# Wireless.net
KiCad netlist of a schematic drawn in Altium Designer
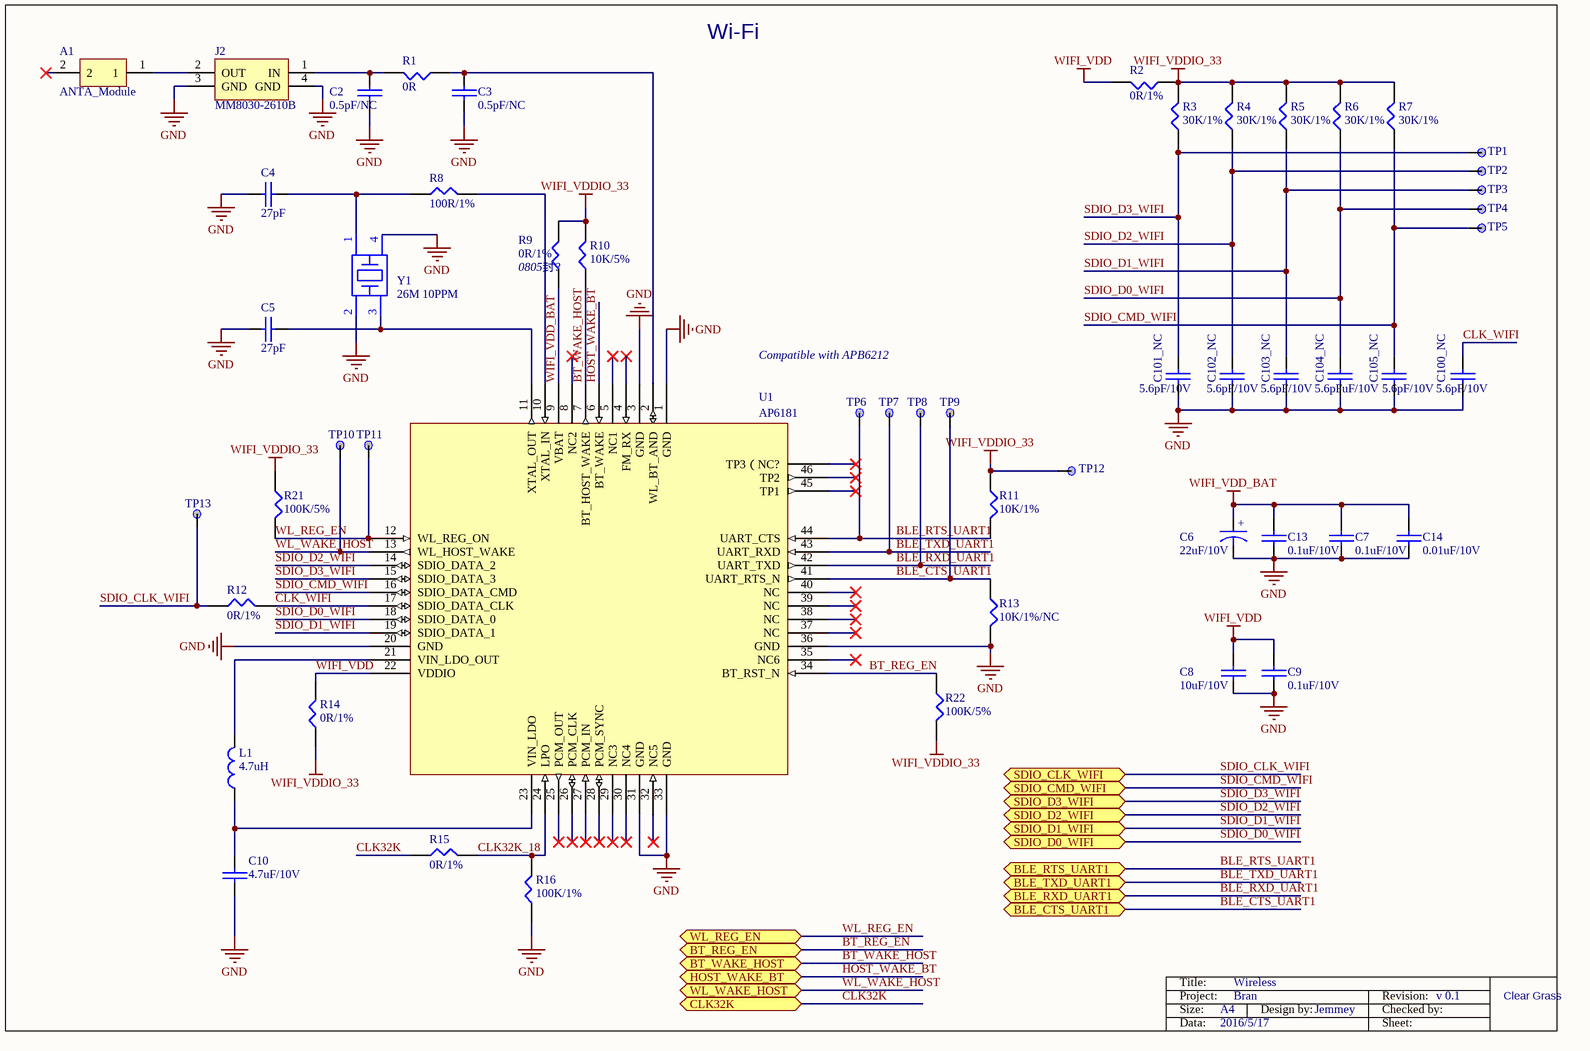
[diagram p0: Wireless.SchDoc]

(export (version "E")
  (design (tool "Eeschema 10.0.6"))
  (components
    (comp (ref "A1")
      (value "ANTA_Module")
      (footprint "IPEX")
      (libsource (lib "Bran MB") (part "ANTA_Module"))
    )
    (comp (ref "C2")
      (value "0.5pF/NC")
      (footprint "0402C")
      (description "厂家：Murata，型号：GRM1555C1H1R0BA01D")
      (libsource (lib "*") (part "CAP"))
    )
    (comp (ref "C3")
      (value "0.5pF/NC")
      (footprint "0402C")
      (description "None")
      (libsource (lib "*") (part "CAP"))
    )
    (comp (ref "C4")
      (value "27pF")
      (footprint "0402C")
      (description "厂家：Murata，型号：GRM155R71A104KA01D")
      (libsource (lib "*") (part "CAP"))
    )
    (comp (ref "C5")
      (value "27pF")
      (footprint "0402C")
      (description "厂家：Murata，型号：GRM155R71A104KA01D")
      (libsource (lib "*") (part "CAP"))
    )
    (comp (ref "C6") (value "22uF/10V") (footprint "6032") (libsource (lib "MoJi LIB") (part "Capacitor")))
    (comp (ref "C7")
      (value "0.1uF/10V")
      (footprint "0402C")
      (description "厂家：Murata，型号：GRM155R71A104KA01D")
      (libsource (lib "Amber") (part "CAP"))
    )
    (comp (ref "C8")
      (value "10uF/10V")
      (footprint "0402C")
      (description "厂家：Murata，型号：GRM155R71A104KA01D")
      (libsource (lib "Amber") (part "CAP"))
    )
    (comp (ref "C9")
      (value "0.1uF/10V")
      (footprint "0402C")
      (description "厂家：Murata，型号：GRM155R71A104KA01D")
      (libsource (lib "Amber") (part "CAP"))
    )
    (comp (ref "C10")
      (value "4.7uF/10V")
      (footprint "0402C")
      (description "厂家：Murata，型号：GRM155R71A104KA01D")
      (libsource (lib "*") (part "CAP"))
    )
    (comp (ref "C13")
      (value "0.1uF/10V")
      (footprint "0402C")
      (description "厂家：Murata，型号：GRM155R71A104KA01D")
      (libsource (lib "Amber") (part "CAP"))
    )
    (comp (ref "C14")
      (value "0.01uF/10V")
      (footprint "0402C")
      (description "厂家：Murata，型号：GRM155R71A104KA01D")
      (libsource (lib "Amber") (part "CAP"))
    )
    (comp (ref "C100_NC")
      (value "5.6pF/10V")
      (footprint "0402C")
      (description "厂家：Murata，型号：GRM155R71A104KA01D")
      (libsource (lib "Amber") (part "CAP"))
    )
    (comp (ref "C101_NC")
      (value "5.6pF/10V")
      (footprint "0402C")
      (description "厂家：Murata，型号：GRM155R71A104KA01D")
      (libsource (lib "Amber") (part "CAP"))
    )
    (comp (ref "C102_NC")
      (value "5.6pF/10V")
      (footprint "0402C")
      (description "厂家：Murata，型号：GRM155R71A104KA01D")
      (libsource (lib "Amber") (part "CAP"))
    )
    (comp (ref "C103_NC")
      (value "5.6pF/10V")
      (footprint "0402C")
      (description "厂家：Murata，型号：GRM155R71A104KA01D")
      (libsource (lib "Amber") (part "CAP"))
    )
    (comp (ref "C104_NC")
      (value "5.6pFuF/10V")
      (footprint "0402C")
      (description "厂家：Murata，型号：GRM155R71A104KA01D")
      (libsource (lib "Amber") (part "CAP"))
    )
    (comp (ref "C105_NC")
      (value "5.6pF/10V")
      (footprint "0402C")
      (description "厂家：Murata，型号：GRM155R71A104KA01D")
      (libsource (lib "Amber") (part "CAP"))
    )
    (comp (ref "J2")
      (value "MM8030-2610B")
      (footprint "IPEX")
      (description "厂家：Murata，型号：MM8030-2610B")
      (libsource (lib "Bran MB") (part "SMA"))
    )
    (comp (ref "L1") (value "4.7uH") (footprint "Inductance") (libsource (lib "*") (part "CHOKE")))
    (comp (ref "R1")
      (value "0R")
      (footprint "0402R")
      (description "厂家：Yageo，型号：RC0402FR-070RL")
      (libsource (lib "*") (part "RES1"))
    )
    (comp (ref "R2")
      (value "0R/1%")
      (footprint "0402R")
      (description "厂家：Yageo，型号：RC0402FR-0710KL")
      (libsource (lib "*") (part "RES1"))
    )
    (comp (ref "R3")
      (value "30K/1%")
      (footprint "0402R")
      (description "厂家：Yageo，型号：RC0402FR-0710KL")
      (libsource (lib "*") (part "RES1"))
    )
    (comp (ref "R4")
      (value "30K/1%")
      (footprint "0402R")
      (description "厂家：Yageo，型号：RC0402FR-0710KL")
      (libsource (lib "*") (part "RES1"))
    )
    (comp (ref "R5")
      (value "30K/1%")
      (footprint "0402R")
      (description "厂家：Yageo，型号：RC0402FR-0710KL")
      (libsource (lib "*") (part "RES1"))
    )
    (comp (ref "R6")
      (value "30K/1%")
      (footprint "0402R")
      (description "厂家：Yageo，型号：RC0402FR-0710KL")
      (libsource (lib "*") (part "RES1"))
    )
    (comp (ref "R7")
      (value "30K/1%")
      (footprint "0402R")
      (description "厂家：Yageo，型号：RC0402FR-0710KL")
      (libsource (lib "*") (part "RES1"))
    )
    (comp (ref "R8")
      (value "100R/1%")
      (footprint "0402R")
      (description "厂家：Yageo，型号：RC0402FR-0710KL")
      (libsource (lib "*") (part "RES1"))
    )
    (comp (ref "R9")
      (value "0R/1%")
      (footprint "0402R")
      (description "厂家：Yageo，型号：RC0402FR-0710KL")
      (libsource (lib "*") (part "RES1"))
    )
    (comp (ref "R10")
      (value "10K/5%")
      (footprint "0402R")
      (description "厂家：Yageo，型号：RC0402FR-0710KL")
      (libsource (lib "*") (part "RES1"))
    )
    (comp (ref "R11")
      (value "10K/1%")
      (footprint "0402R")
      (description "厂家：Yageo，型号：RC0402FR-0710KL")
      (libsource (lib "*") (part "RES1"))
    )
    (comp (ref "R12")
      (value "0R/1%")
      (footprint "0402R")
      (description "厂家：Yageo，型号：RC0402FR-0710KL")
      (libsource (lib "*") (part "RES1"))
    )
    (comp (ref "R13")
      (value "10K/1%/NC")
      (footprint "0402R")
      (description "厂家：Yageo，型号：RC0402FR-0710KL")
      (libsource (lib "*") (part "RES1"))
    )
    (comp (ref "R14")
      (value "0R/1%")
      (footprint "0402R")
      (description "厂家：Yageo，型号：RC0402FR-0710KL")
      (libsource (lib "*") (part "RES1"))
    )
    (comp (ref "R15")
      (value "0R/1%")
      (footprint "0402R")
      (description "厂家：Yageo，型号：RC0402FR-0710KL")
      (libsource (lib "*") (part "RES1"))
    )
    (comp (ref "R16")
      (value "100K/1%")
      (footprint "0402R")
      (description "厂家：Yageo，型号：RC0402FR-0710KL")
      (libsource (lib "*") (part "RES1"))
    )
    (comp (ref "R21")
      (value "100K/5%")
      (footprint "0402R")
      (description "厂家：Yageo，型号：RC0402FR-0710KL")
      (libsource (lib "*") (part "RES1"))
    )
    (comp (ref "R22")
      (value "100K/5%")
      (footprint "0402R")
      (description "厂家：Yageo，型号：RC0402FR-0710KL")
      (libsource (lib "*") (part "RES1"))
    )
    (comp (ref "TP1") (value "TP") (footprint "TP_C40") (libsource (lib "Almos") (part "TP")))
    (comp (ref "TP2") (value "TP") (footprint "TP_C40") (libsource (lib "Almos") (part "TP")))
    (comp (ref "TP3") (value "TP") (footprint "TP_C40") (libsource (lib "Almos") (part "TP")))
    (comp (ref "TP4") (value "TP") (footprint "TP_C40") (libsource (lib "Almos") (part "TP")))
    (comp (ref "TP5") (value "TP") (footprint "TP_C40") (libsource (lib "Almos") (part "TP")))
    (comp (ref "TP6") (value "TP") (footprint "TP_C40") (libsource (lib "Almos") (part "TP")))
    (comp (ref "TP7") (value "TP") (footprint "TP_C40") (libsource (lib "Almos") (part "TP")))
    (comp (ref "TP8") (value "TP") (footprint "TP_C40") (libsource (lib "Almos") (part "TP")))
    (comp (ref "TP9") (value "TP") (footprint "TP_C40") (libsource (lib "Almos") (part "TP")))
    (comp (ref "TP10") (value "TP") (footprint "TP_C40") (libsource (lib "Almos") (part "TP")))
    (comp (ref "TP11") (value "TP") (footprint "TP_C40") (libsource (lib "Almos") (part "TP")))
    (comp (ref "TP12") (value "TP") (footprint "TP_C40") (libsource (lib "Almos") (part "TP")))
    (comp (ref "TP13") (value "TP") (footprint "TP_C40") (libsource (lib "Almos") (part "TP")))
    (comp (ref "U1")
      (value "AP6181")
      (description "厂家：正基，型号：AP6181")
      (libsource (lib "Bran MB") (part "AP6181"))
    )
    (comp (ref "Y1")
      (value "26M 10PPM")
      (footprint "XTALSMD2-2520")
      (description "厂家：EPSON，型号：Q24FA20H0004400")
      (libsource (lib "Amber_1") (part "CRYSTAL2"))
    )
  )
  (nets
    (net (code "1") (name "/BLE_CTS_UART1") (class "Default")
      (node (ref "R13") (pin "1") (pinfunction "1_1") (pintype "passive"))
      (node (ref "TP9") (pin "1") (pinfunction "1_1") (pintype "passive"))
      (node (ref "U1") (pin "41") (pinfunction "UART_RTS_N_41") (pintype "output"))
    )
    (net (code "2") (name "/BLE_RTS_UART1") (class "Default")
      (node (ref "R11") (pin "2") (pinfunction "2_2") (pintype "passive"))
      (node (ref "TP6") (pin "1") (pinfunction "1_1") (pintype "passive"))
      (node (ref "U1") (pin "44") (pinfunction "UART_CTS_44") (pintype "input"))
    )
    (net (code "3") (name "/BLE_RXD_UART1") (class "Default")
      (node (ref "TP8") (pin "1") (pinfunction "1_1") (pintype "passive"))
      (node (ref "U1") (pin "42") (pinfunction "UART_TXD_42") (pintype "output"))
    )
    (net (code "4") (name "/BLE_TXD_UART1") (class "Default")
      (node (ref "TP7") (pin "1") (pinfunction "1_1") (pintype "passive"))
      (node (ref "U1") (pin "43") (pinfunction "UART_RXD_43") (pintype "input"))
    )
    (net (code "5") (name "/BT_REG_EN") (class "Default")
      (node (ref "R22") (pin "1") (pinfunction "1_1") (pintype "passive"))
      (node (ref "U1") (pin "34") (pinfunction "BT_RST_N_34") (pintype "input"))
    )
    (net (code "6") (name "/BT_WAKE_HOST") (class "Default")
      (node (ref "R10") (pin "1") (pinfunction "1_1") (pintype "passive"))
      (node (ref "U1") (pin "7") (pinfunction "BT_HOST_WAKE_7") (pintype "output"))
    )
    (net (code "7") (name "/CLK32K") (class "Default")
      (node (ref "R15") (pin "1") (pinfunction "1_1") (pintype "passive"))
    )
    (net (code "8") (name "/CLK32K_18") (class "Default")
      (node (ref "R15") (pin "2") (pinfunction "2_2") (pintype "passive"))
      (node (ref "R16") (pin "2") (pinfunction "2_2") (pintype "passive"))
      (node (ref "U1") (pin "24") (pinfunction "LPO_24") (pintype "input"))
    )
    (net (code "9") (name "/CLK_WIFI") (class "Default")
      (node (ref "C100_NC") (pin "2") (pinfunction "2_2") (pintype "passive"))
      (node (ref "R12") (pin "2") (pinfunction "2_2") (pintype "passive"))
      (node (ref "U1") (pin "17") (pinfunction "SDIO_DATA_CLK_17") (pintype "bidirectional"))
    )
    (net (code "10") (name "/HOST_WAKE_BT") (class "Default")
      (node (ref "U1") (pin "6") (pinfunction "BT_WAKE_6") (pintype "input"))
    )
    (net (code "11") (name "/SDIO_CLK_WIFI") (class "Default")
      (node (ref "R12") (pin "1") (pinfunction "1_1") (pintype "passive"))
      (node (ref "TP13") (pin "1") (pinfunction "1_1") (pintype "passive"))
    )
    (net (code "12") (name "/SDIO_CMD_WIFI") (class "Default")
      (node (ref "C105_NC") (pin "2") (pinfunction "2_2") (pintype "passive"))
      (node (ref "R7") (pin "1") (pinfunction "1_1") (pintype "passive"))
      (node (ref "TP5") (pin "1") (pinfunction "1_1") (pintype "passive"))
      (node (ref "U1") (pin "16") (pinfunction "SDIO_DATA_CMD_16") (pintype "bidirectional"))
    )
    (net (code "13") (name "/SDIO_D0_WIFI") (class "Default")
      (node (ref "C104_NC") (pin "2") (pinfunction "2_2") (pintype "passive"))
      (node (ref "R6") (pin "1") (pinfunction "1_1") (pintype "passive"))
      (node (ref "TP4") (pin "1") (pinfunction "1_1") (pintype "passive"))
      (node (ref "U1") (pin "18") (pinfunction "SDIO_DATA_0_18") (pintype "bidirectional"))
    )
    (net (code "14") (name "/SDIO_D1_WIFI") (class "Default")
      (node (ref "C103_NC") (pin "2") (pinfunction "2_2") (pintype "passive"))
      (node (ref "R5") (pin "1") (pinfunction "1_1") (pintype "passive"))
      (node (ref "TP3") (pin "1") (pinfunction "1_1") (pintype "passive"))
      (node (ref "U1") (pin "19") (pinfunction "SDIO_DATA_1_19") (pintype "bidirectional"))
    )
    (net (code "15") (name "/SDIO_D2_WIFI") (class "Default")
      (node (ref "C102_NC") (pin "2") (pinfunction "2_2") (pintype "passive"))
      (node (ref "R4") (pin "1") (pinfunction "1_1") (pintype "passive"))
      (node (ref "TP2") (pin "1") (pinfunction "1_1") (pintype "passive"))
      (node (ref "U1") (pin "14") (pinfunction "SDIO_DATA_2_14") (pintype "bidirectional"))
    )
    (net (code "16") (name "/SDIO_D3_WIFI") (class "Default")
      (node (ref "C101_NC") (pin "2") (pinfunction "2_2") (pintype "passive"))
      (node (ref "R3") (pin "1") (pinfunction "1_1") (pintype "passive"))
      (node (ref "TP1") (pin "1") (pinfunction "1_1") (pintype "passive"))
      (node (ref "U1") (pin "15") (pinfunction "SDIO_DATA_3_15") (pintype "bidirectional"))
    )
    (net (code "17") (name "/WL_REG_EN") (class "Default")
      (node (ref "R21") (pin "2") (pinfunction "2_2") (pintype "passive"))
      (node (ref "TP11") (pin "1") (pinfunction "1_1") (pintype "passive"))
      (node (ref "U1") (pin "12") (pinfunction "WL_REG_ON_12") (pintype "input"))
    )
    (net (code "18") (name "/WL_WAKE_HOST") (class "Default")
      (node (ref "TP10") (pin "1") (pinfunction "1_1") (pintype "passive"))
      (node (ref "U1") (pin "13") (pinfunction "WL_HOST_WAKE_13") (pintype "output"))
    )
    (net (code "19") (name "GND") (class "Default")
      (node (ref "C10") (pin "2") (pinfunction "2_2") (pintype "passive"))
      (node (ref "C100_NC") (pin "1") (pinfunction "1_1") (pintype "passive"))
      (node (ref "C101_NC") (pin "1") (pinfunction "1_1") (pintype "passive"))
      (node (ref "C102_NC") (pin "1") (pinfunction "1_1") (pintype "passive"))
      (node (ref "C103_NC") (pin "1") (pinfunction "1_1") (pintype "passive"))
      (node (ref "C104_NC") (pin "1") (pinfunction "1_1") (pintype "passive"))
      (node (ref "C105_NC") (pin "1") (pinfunction "1_1") (pintype "passive"))
      (node (ref "C13") (pin "1") (pinfunction "1_1") (pintype "passive"))
      (node (ref "C14") (pin "1") (pinfunction "1_1") (pintype "passive"))
      (node (ref "C2") (pin "2") (pinfunction "2_2") (pintype "passive"))
      (node (ref "C3") (pin "2") (pinfunction "2_2") (pintype "passive"))
      (node (ref "C4") (pin "1") (pinfunction "1_1") (pintype "passive"))
      (node (ref "C5") (pin "1") (pinfunction "1_1") (pintype "passive"))
      (node (ref "C6") (pin "2") (pinfunction "2_2") (pintype "passive"))
      (node (ref "C7") (pin "1") (pinfunction "1_1") (pintype "passive"))
      (node (ref "C8") (pin "1") (pinfunction "1_1") (pintype "passive"))
      (node (ref "C9") (pin "1") (pinfunction "1_1") (pintype "passive"))
      (node (ref "J2") (pin "3") (pinfunction "GND_3") (pintype "passive"))
      (node (ref "J2") (pin "4") (pinfunction "GND_4") (pintype "passive"))
      (node (ref "R13") (pin "2") (pinfunction "2_2") (pintype "passive"))
      (node (ref "R16") (pin "1") (pinfunction "1_1") (pintype "passive"))
      (node (ref "U1") (pin "1") (pinfunction "GND_1") (pintype "power_in"))
      (node (ref "U1") (pin "20") (pinfunction "GND_20") (pintype "power_in"))
      (node (ref "U1") (pin "3") (pinfunction "GND_3") (pintype "power_in"))
      (node (ref "U1") (pin "31") (pinfunction "GND_31") (pintype "power_in"))
      (node (ref "U1") (pin "33") (pinfunction "GND_33") (pintype "power_in"))
      (node (ref "U1") (pin "36") (pinfunction "GND_36") (pintype "passive"))
      (node (ref "Y1") (pin "2") (pinfunction "2_2") (pintype "passive"))
      (node (ref "Y1") (pin "4") (pinfunction "4_4") (pintype "passive"))
    )
    (net (code "20") (name "Net-(C4-Pad2)") (class "Default")
      (node (ref "C4") (pin "2") (pinfunction "2_2") (pintype "passive"))
      (node (ref "R8") (pin "1") (pinfunction "1_1") (pintype "passive"))
      (node (ref "Y1") (pin "1") (pinfunction "1_1") (pintype "passive"))
    )
    (net (code "21") (name "Net-(J2-IN)") (class "Default")
      (node (ref "C2") (pin "1") (pinfunction "1_1") (pintype "passive"))
      (node (ref "J2") (pin "1") (pinfunction "IN_1") (pintype "passive"))
      (node (ref "R1") (pin "2") (pinfunction "2_2") (pintype "passive"))
    )
    (net (code "22") (name "Net-(J2-OUT)") (class "Default")
      (node (ref "A1") (pin "1") (pinfunction "1_1") (pintype "passive"))
      (node (ref "J2") (pin "2") (pinfunction "OUT_2") (pintype "passive"))
    )
    (net (code "23") (name "Net-(U1-VIN_LDO)") (class "Default")
      (node (ref "C10") (pin "1") (pinfunction "1_1") (pintype "passive"))
      (node (ref "L1") (pin "1") (pinfunction "1_1") (pintype "passive"))
      (node (ref "U1") (pin "23") (pinfunction "VIN_LDO_23") (pintype "power_in"))
    )
    (net (code "24") (name "Net-(U1-VIN_LDO_OUT)") (class "Default")
      (node (ref "L1") (pin "2") (pinfunction "2_2") (pintype "passive"))
      (node (ref "U1") (pin "21") (pinfunction "VIN_LDO_OUT_21") (pintype "power_in"))
    )
    (net (code "25") (name "Net-(U1-WL_BT_AND)") (class "Default")
      (node (ref "C3") (pin "1") (pinfunction "1_1") (pintype "passive"))
      (node (ref "R1") (pin "1") (pinfunction "1_1") (pintype "passive"))
      (node (ref "U1") (pin "2") (pinfunction "WL_BT_AND_2") (pintype "bidirectional"))
    )
    (net (code "26") (name "Net-(U1-XTAL_IN)") (class "Default")
      (node (ref "R8") (pin "2") (pinfunction "2_2") (pintype "passive"))
      (node (ref "U1") (pin "10") (pinfunction "XTAL_IN_10") (pintype "input"))
    )
    (net (code "27") (name "Net-(U1-XTAL_OUT)") (class "Default")
      (node (ref "C5") (pin "2") (pinfunction "2_2") (pintype "passive"))
      (node (ref "U1") (pin "11") (pinfunction "XTAL_OUT_11") (pintype "output"))
      (node (ref "Y1") (pin "3") (pinfunction "3_3") (pintype "passive"))
    )
    (net (code "28") (name "WIFI_VDD") (class "Default")
      (node (ref "C8") (pin "2") (pinfunction "2_2") (pintype "passive"))
      (node (ref "C9") (pin "2") (pinfunction "2_2") (pintype "passive"))
      (node (ref "R14") (pin "2") (pinfunction "2_2") (pintype "passive"))
      (node (ref "R2") (pin "2") (pinfunction "2_2") (pintype "passive"))
      (node (ref "U1") (pin "22") (pinfunction "VDDIO_22") (pintype "power_in"))
    )
    (net (code "29") (name "WIFI_VDDIO_33") (class "Default")
      (node (ref "R10") (pin "2") (pinfunction "2_2") (pintype "passive"))
      (node (ref "R11") (pin "1") (pinfunction "1_1") (pintype "passive"))
      (node (ref "R14") (pin "1") (pinfunction "1_1") (pintype "passive"))
      (node (ref "R2") (pin "1") (pinfunction "1_1") (pintype "passive"))
      (node (ref "R21") (pin "1") (pinfunction "1_1") (pintype "passive"))
      (node (ref "R22") (pin "2") (pinfunction "2_2") (pintype "passive"))
      (node (ref "R3") (pin "2") (pinfunction "2_2") (pintype "passive"))
      (node (ref "R4") (pin "2") (pinfunction "2_2") (pintype "passive"))
      (node (ref "R5") (pin "2") (pinfunction "2_2") (pintype "passive"))
      (node (ref "R6") (pin "2") (pinfunction "2_2") (pintype "passive"))
      (node (ref "R7") (pin "2") (pinfunction "2_2") (pintype "passive"))
      (node (ref "R9") (pin "2") (pinfunction "2_2") (pintype "passive"))
      (node (ref "TP12") (pin "1") (pinfunction "1_1") (pintype "passive"))
    )
    (net (code "30") (name "WIFI_VDD_BAT") (class "Default")
      (node (ref "C13") (pin "2") (pinfunction "2_2") (pintype "passive"))
      (node (ref "C14") (pin "2") (pinfunction "2_2") (pintype "passive"))
      (node (ref "C6") (pin "1") (pinfunction "1_1") (pintype "passive"))
      (node (ref "C7") (pin "2") (pinfunction "2_2") (pintype "passive"))
      (node (ref "R9") (pin "1") (pinfunction "1_1") (pintype "passive"))
      (node (ref "U1") (pin "9") (pinfunction "VBAT_9") (pintype "power_in"))
    )
    (net (code "31") (name "unconnected-(A1-Pad2)") (class "Default")
      (node (ref "A1") (pin "2") (pinfunction "2_2") (pintype "passive+no_connect"))
    )
    (net (code "32") (name "unconnected-(U1-FM_RX-Pad4)") (class "Default")
      (node (ref "U1") (pin "4") (pinfunction "FM_RX_4") (pintype "input+no_connect"))
    )
    (net (code "33") (name "unconnected-(U1-NC-Pad37)") (class "Default")
      (node (ref "U1") (pin "37") (pinfunction "NC_37") (pintype "passive+no_connect"))
    )
    (net (code "34") (name "unconnected-(U1-NC-Pad38)") (class "Default")
      (node (ref "U1") (pin "38") (pinfunction "NC_38") (pintype "passive+no_connect"))
    )
    (net (code "35") (name "unconnected-(U1-NC-Pad39)") (class "Default")
      (node (ref "U1") (pin "39") (pinfunction "NC_39") (pintype "passive+no_connect"))
    )
    (net (code "36") (name "unconnected-(U1-NC-Pad40)") (class "Default")
      (node (ref "U1") (pin "40") (pinfunction "NC_40") (pintype "passive+no_connect"))
    )
    (net (code "37") (name "unconnected-(U1-NC1-Pad5)") (class "Default")
      (node (ref "U1") (pin "5") (pinfunction "NC1_5") (pintype "passive+no_connect"))
    )
    (net (code "38") (name "unconnected-(U1-NC2-Pad8)") (class "Default")
      (node (ref "U1") (pin "8") (pinfunction "NC2_8") (pintype "passive+no_connect"))
    )
    (net (code "39") (name "unconnected-(U1-NC3-Pad29)") (class "Default")
      (node (ref "U1") (pin "29") (pinfunction "NC3_29") (pintype "passive+no_connect"))
    )
    (net (code "40") (name "unconnected-(U1-NC4-Pad30)") (class "Default")
      (node (ref "U1") (pin "30") (pinfunction "NC4_30") (pintype "passive+no_connect"))
    )
    (net (code "41") (name "unconnected-(U1-NC5-Pad32)") (class "Default")
      (node (ref "U1") (pin "32") (pinfunction "NC5_32") (pintype "input+no_connect"))
    )
    (net (code "42") (name "unconnected-(U1-NC6-Pad35)") (class "Default")
      (node (ref "U1") (pin "35") (pinfunction "NC6_35") (pintype "passive+no_connect"))
    )
    (net (code "43") (name "unconnected-(U1-PCM_CLK-Pad26)") (class "Default")
      (node (ref "U1") (pin "26") (pinfunction "PCM_CLK_26") (pintype "bidirectional+no_connect"))
    )
    (net (code "44") (name "unconnected-(U1-PCM_IN-Pad27)") (class "Default")
      (node (ref "U1") (pin "27") (pinfunction "PCM_IN_27") (pintype "input+no_connect"))
    )
    (net (code "45") (name "unconnected-(U1-PCM_OUT-Pad25)") (class "Default")
      (node (ref "U1") (pin "25") (pinfunction "PCM_OUT_25") (pintype "output+no_connect"))
    )
    (net (code "46") (name "unconnected-(U1-PCM_SYNC-Pad28)") (class "Default")
      (node (ref "U1") (pin "28") (pinfunction "PCM_SYNC_28") (pintype "bidirectional+no_connect"))
    )
    (net (code "47") (name "unconnected-(U1-TP1-Pad45)") (class "Default")
      (node (ref "U1") (pin "45") (pinfunction "TP1_45") (pintype "output+no_connect"))
    )
    (net (code "48") (name "unconnected-(U1-TP2-Pad46)") (class "Default")
      (node (ref "U1") (pin "46") (pinfunction "TP2_46") (pintype "output+no_connect"))
    )
    (net (code "49") (name "unconnected-(U1-TP3（NC?-Pad)") (class "Default")
      (node (ref "U1") (pin "") (pinfunction "TP3（NC?_") (pintype "passive+no_connect"))
    )
  )
)
